# camera.net
KiCad netlist of a schematic drawn in Altium Designer
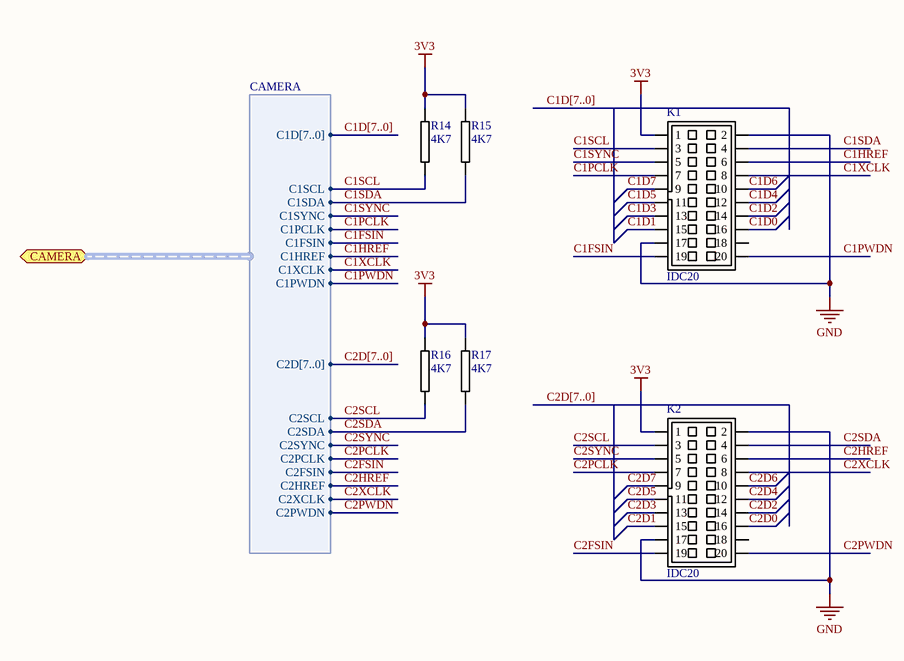
[diagram p0: camera.SchDoc]

(export (version "E")
  (design (tool "Eeschema 10.0.6"))
  (components
    (comp (ref "K1")
      (value "IDC20")
      (footprint "TH Connectors:HEADER20_FEMALE")
      (description "CONN HEADER LOW-PRO 20POS GOLD")
      (fields (field (name "MANUFACTURER") "Assmann Electronics Inc"))
      (libsource (lib "vh_Altium Library") (part "IDC20"))
    )
    (comp (ref "K2")
      (value "IDC20")
      (footprint "TH Connectors:HEADER20_FEMALE")
      (description "CONN HEADER LOW-PRO 20POS GOLD")
      (fields (field (name "MANUFACTURER") "Assmann Electronics Inc"))
      (libsource (lib "vh_Altium Library") (part "IDC20"))
    )
    (comp (ref "R14")
      (value "4K7")
      (footprint "0603R-4K7")
      (description "GENERIC RESISTOR 0603")
      (fields
        (field (name "MANUFACTURER") "Stackpole Electronics Inc")
        (field (name "MANUFACTURER PART NUMBER") "RMCF 1/16 4.7K 1% R")
      )
      (libsource (lib "vh_Altium Library") (part "0603R-4K7"))
    )
    (comp (ref "R15")
      (value "4K7")
      (footprint "0603R-4K7")
      (description "GENERIC RESISTOR 0603")
      (fields
        (field (name "MANUFACTURER") "Stackpole Electronics Inc")
        (field (name "MANUFACTURER PART NUMBER") "RMCF 1/16 4.7K 1% R")
      )
      (libsource (lib "vh_Altium Library") (part "0603R-4K7"))
    )
    (comp (ref "R16")
      (value "4K7")
      (footprint "0603R-4K7")
      (description "GENERIC RESISTOR 0603")
      (fields
        (field (name "MANUFACTURER") "Stackpole Electronics Inc")
        (field (name "MANUFACTURER PART NUMBER") "RMCF 1/16 4.7K 1% R")
      )
      (libsource (lib "vh_Altium Library") (part "0603R-4K7"))
    )
    (comp (ref "R17")
      (value "4K7")
      (footprint "0603R-4K7")
      (description "GENERIC RESISTOR 0603")
      (fields
        (field (name "MANUFACTURER") "Stackpole Electronics Inc")
        (field (name "MANUFACTURER PART NUMBER") "RMCF 1/16 4.7K 1% R")
      )
      (libsource (lib "vh_Altium Library") (part "0603R-4K7"))
    )
  )
  (nets
    (net (code "2") (name "/C1D0") (class "Default")
      (node (ref "K1") (pin "16") (pinfunction "16_16") (pintype "passive"))
    )
    (net (code "3") (name "/C1D1") (class "Default")
      (node (ref "K1") (pin "15") (pinfunction "15_15") (pintype "passive"))
    )
    (net (code "4") (name "/C1D2") (class "Default")
      (node (ref "K1") (pin "14") (pinfunction "14_14") (pintype "passive"))
    )
    (net (code "5") (name "/C1D3") (class "Default")
      (node (ref "K1") (pin "13") (pinfunction "13_13") (pintype "passive"))
    )
    (net (code "6") (name "/C1D4") (class "Default")
      (node (ref "K1") (pin "12") (pinfunction "12_12") (pintype "passive"))
    )
    (net (code "7") (name "/C1D5") (class "Default")
      (node (ref "K1") (pin "11") (pinfunction "11_11") (pintype "passive"))
    )
    (net (code "8") (name "/C1D6") (class "Default")
      (node (ref "K1") (pin "10") (pinfunction "10_10") (pintype "passive"))
    )
    (net (code "9") (name "/C1D7") (class "Default")
      (node (ref "K1") (pin "9") (pinfunction "9_9") (pintype "passive"))
    )
    (net (code "11") (name "/C1FSIN") (class "Default")
      (node (ref "K1") (pin "19") (pinfunction "19_19") (pintype "passive"))
    )
    (net (code "12") (name "/C1HREF") (class "Default")
      (node (ref "K1") (pin "6") (pinfunction "6_6") (pintype "passive"))
    )
    (net (code "13") (name "/C1PCLK") (class "Default")
      (node (ref "K1") (pin "7") (pinfunction "7_7") (pintype "passive"))
    )
    (net (code "14") (name "/C1PWDN") (class "Default")
      (node (ref "K1") (pin "20") (pinfunction "20_20") (pintype "passive"))
    )
    (net (code "15") (name "/C1SCL") (class "Default")
      (node (ref "K1") (pin "3") (pinfunction "3_3") (pintype "passive"))
      (node (ref "R14") (pin "2") (pintype "passive"))
    )
    (net (code "16") (name "/C1SDA") (class "Default")
      (node (ref "K1") (pin "4") (pinfunction "4_4") (pintype "passive"))
      (node (ref "R15") (pin "2") (pintype "passive"))
    )
    (net (code "17") (name "/C1SYNC") (class "Default")
      (node (ref "K1") (pin "5") (pinfunction "5_5") (pintype "passive"))
    )
    (net (code "18") (name "/C1XCLK") (class "Default")
      (node (ref "K1") (pin "8") (pinfunction "8_8") (pintype "passive"))
    )
    (net (code "19") (name "/C2D0") (class "Default")
      (node (ref "K2") (pin "16") (pinfunction "16_16") (pintype "passive"))
    )
    (net (code "20") (name "/C2D1") (class "Default")
      (node (ref "K2") (pin "15") (pinfunction "15_15") (pintype "passive"))
    )
    (net (code "21") (name "/C2D2") (class "Default")
      (node (ref "K2") (pin "14") (pinfunction "14_14") (pintype "passive"))
    )
    (net (code "22") (name "/C2D3") (class "Default")
      (node (ref "K2") (pin "13") (pinfunction "13_13") (pintype "passive"))
    )
    (net (code "23") (name "/C2D4") (class "Default")
      (node (ref "K2") (pin "12") (pinfunction "12_12") (pintype "passive"))
    )
    (net (code "24") (name "/C2D5") (class "Default")
      (node (ref "K2") (pin "11") (pinfunction "11_11") (pintype "passive"))
    )
    (net (code "25") (name "/C2D6") (class "Default")
      (node (ref "K2") (pin "10") (pinfunction "10_10") (pintype "passive"))
    )
    (net (code "26") (name "/C2D7") (class "Default")
      (node (ref "K2") (pin "9") (pinfunction "9_9") (pintype "passive"))
    )
    (net (code "28") (name "/C2FSIN") (class "Default")
      (node (ref "K2") (pin "19") (pinfunction "19_19") (pintype "passive"))
    )
    (net (code "29") (name "/C2HREF") (class "Default")
      (node (ref "K2") (pin "6") (pinfunction "6_6") (pintype "passive"))
    )
    (net (code "30") (name "/C2PCLK") (class "Default")
      (node (ref "K2") (pin "7") (pinfunction "7_7") (pintype "passive"))
    )
    (net (code "31") (name "/C2PWDN") (class "Default")
      (node (ref "K2") (pin "20") (pinfunction "20_20") (pintype "passive"))
    )
    (net (code "32") (name "/C2SCL") (class "Default")
      (node (ref "K2") (pin "3") (pinfunction "3_3") (pintype "passive"))
      (node (ref "R16") (pin "2") (pintype "passive"))
    )
    (net (code "33") (name "/C2SDA") (class "Default")
      (node (ref "K2") (pin "4") (pinfunction "4_4") (pintype "passive"))
      (node (ref "R17") (pin "2") (pintype "passive"))
    )
    (net (code "34") (name "/C2SYNC") (class "Default")
      (node (ref "K2") (pin "5") (pinfunction "5_5") (pintype "passive"))
    )
    (net (code "35") (name "/C2XCLK") (class "Default")
      (node (ref "K2") (pin "8") (pinfunction "8_8") (pintype "passive"))
    )
    (net (code "37") (name "3V3") (class "Default")
      (node (ref "K1") (pin "1") (pinfunction "1_1") (pintype "passive"))
      (node (ref "K2") (pin "1") (pinfunction "1_1") (pintype "passive"))
      (node (ref "R14") (pin "1") (pintype "passive"))
      (node (ref "R15") (pin "1") (pintype "passive"))
      (node (ref "R16") (pin "1") (pintype "passive"))
      (node (ref "R17") (pin "1") (pintype "passive"))
    )
    (net (code "38") (name "GND") (class "Default")
      (node (ref "K1") (pin "17") (pinfunction "17_17") (pintype "passive"))
      (node (ref "K1") (pin "2") (pinfunction "2_2") (pintype "passive"))
      (node (ref "K2") (pin "17") (pinfunction "17_17") (pintype "passive"))
      (node (ref "K2") (pin "2") (pinfunction "2_2") (pintype "passive"))
    )
    (net (code "39") (name "unconnected-(K1-Pad18)") (class "Default")
      (node (ref "K1") (pin "18") (pinfunction "18_18") (pintype "passive"))
    )
    (net (code "40") (name "unconnected-(K2-Pad18)") (class "Default")
      (node (ref "K2") (pin "18") (pinfunction "18_18") (pintype "passive"))
    )
  )
)
